# LDOC_sch.net
KiCad netlist of a schematic drawn in Altium Designer
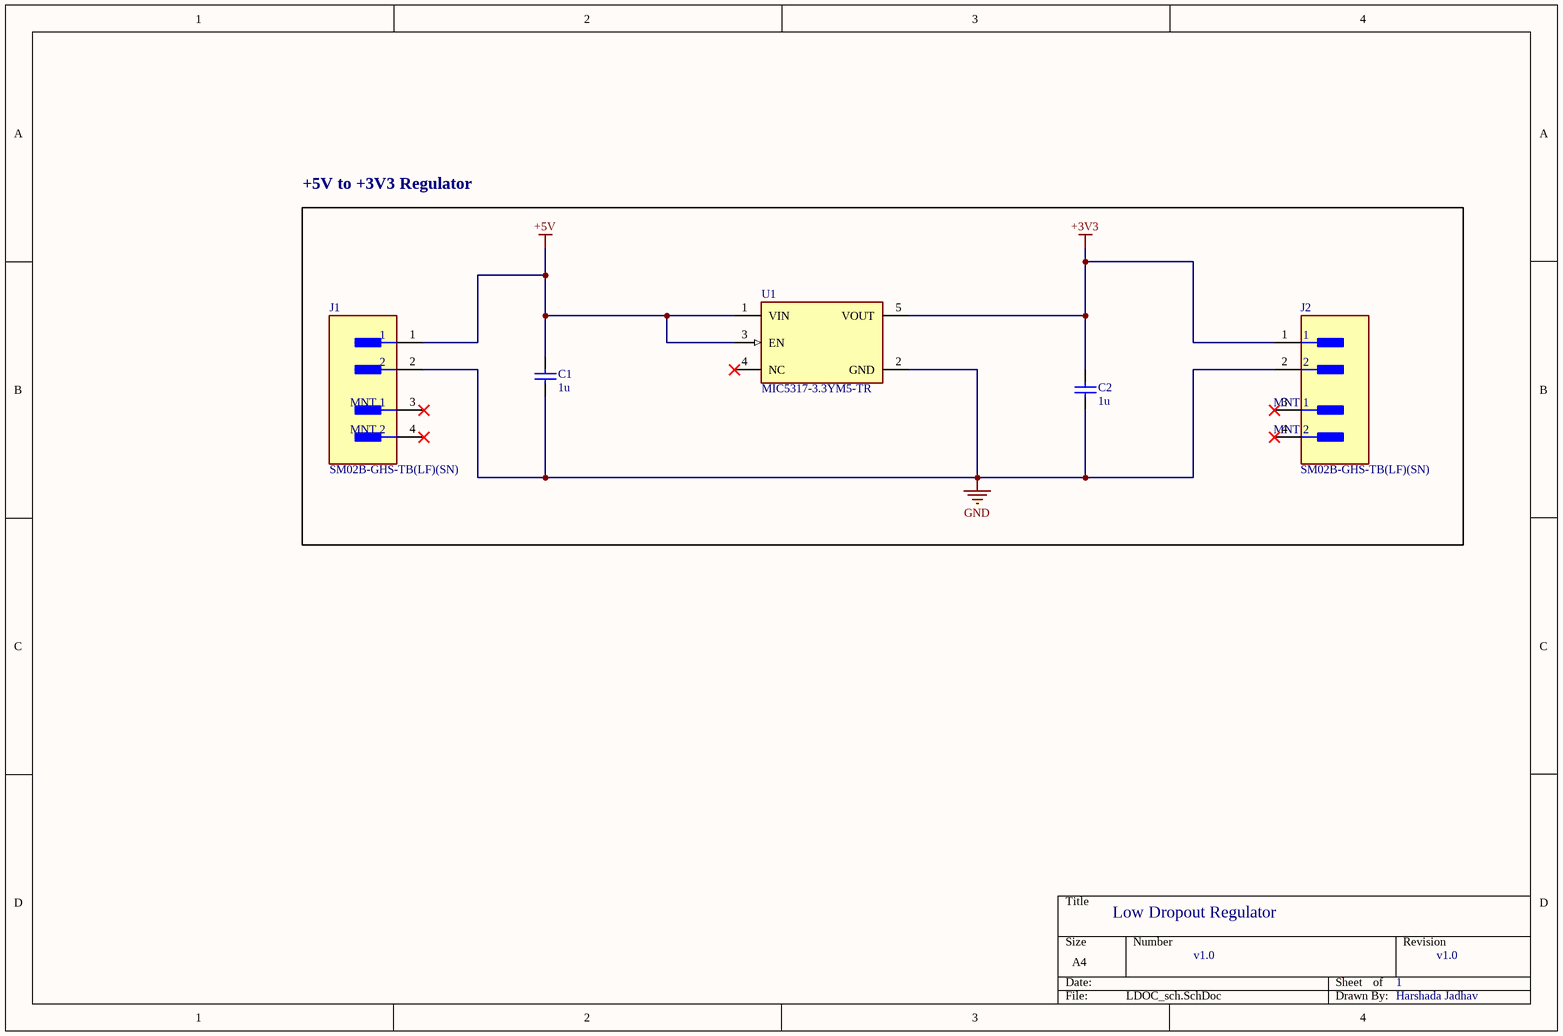
[diagram p0: LDOC_sch.SchDoc]

(export (version "E")
  (design (tool "Eeschema 10.0.6"))
  (components
    (comp (ref "C1")
      (value "1u")
      (footprint "CAPC2013X145X50ML20T25")
      (fields (field (name "PART NUMBER") "C0805C105K8RALTU") (field (name "MANUFACTURER") "Kemet"))
      (libsource (lib "Altium Content Vault") (part "CAP"))
    )
    (comp (ref "C2")
      (value "1u")
      (footprint "CAPC2013X145X50ML20T25")
      (fields (field (name "PART NUMBER") "C0805C105K8RALTU") (field (name "MANUFACTURER") "Kemet"))
      (libsource (lib "Altium Content Vault") (part "CAP"))
    )
    (comp (ref "J1")
      (value "SM02B-GHS-TB(LF)(SN)")
      (footprint "FP-SM02B-GHS-TB_LF_SN-MFG")
      (description "CONN HEADER SMD R/A 2POS 1.25MM")
      (libsource (lib "Altium Content Vault") (part "56ec3178a87b3978bdc1b3682cd516a"))
    )
    (comp (ref "J2")
      (value "SM02B-GHS-TB(LF)(SN)")
      (footprint "FP-SM02B-GHS-TB_LF_SN-MFG")
      (description "CONN HEADER SMD R/A 2POS 1.25MM")
      (libsource (lib "") (part "56ec3178a87b3978bdc1b3682cd516a_1"))
    )
    (comp (ref "U1")
      (value "MIC5317-3.3YM5-TR")
      (footprint "FP-SOT23-5LD-PL-1-MFG")
      (description "IC REG LINEAR 3.3V 150MA SOT23-5")
      (libsource (lib "Altium Content Vault") (part "0a093dae7315cdc977fd108dde87457"))
    )
  )
  (nets
    (net (code "1") (name "+3V3") (class "Default")
      (node (ref "C2") (pin "1") (pinfunction "1_1") (pintype "passive"))
      (node (ref "J2") (pin "1") (pinfunction "1_1") (pintype "passive"))
      (node (ref "U1") (pin "5") (pinfunction "VOUT_5") (pintype "power_in"))
    )
    (net (code "2") (name "+5V") (class "Default")
      (node (ref "C1") (pin "1") (pinfunction "1_1") (pintype "passive"))
      (node (ref "J1") (pin "1") (pinfunction "1_1") (pintype "passive"))
      (node (ref "U1") (pin "1") (pinfunction "VIN_1") (pintype "power_in"))
      (node (ref "U1") (pin "3") (pinfunction "EN_3") (pintype "input"))
    )
    (net (code "3") (name "GND") (class "Default")
      (node (ref "C1") (pin "2") (pinfunction "2_2") (pintype "passive"))
      (node (ref "C2") (pin "2") (pinfunction "2_2") (pintype "passive"))
      (node (ref "J1") (pin "2") (pinfunction "2_2") (pintype "passive"))
      (node (ref "J2") (pin "2") (pinfunction "2_2") (pintype "passive"))
      (node (ref "U1") (pin "2") (pinfunction "GND_2") (pintype "power_in"))
    )
    (net (code "4") (name "unconnected-(J1-MNT_1-Pad3)") (class "Default")
      (node (ref "J1") (pin "3") (pinfunction "MNT_1_3") (pintype "passive+no_connect"))
    )
    (net (code "5") (name "unconnected-(J1-MNT_2-Pad4)") (class "Default")
      (node (ref "J1") (pin "4") (pinfunction "MNT_2_4") (pintype "passive+no_connect"))
    )
    (net (code "6") (name "unconnected-(J2-MNT_1-Pad3)") (class "Default")
      (node (ref "J2") (pin "3") (pinfunction "MNT_1_3") (pintype "passive+no_connect"))
    )
    (net (code "7") (name "unconnected-(J2-MNT_2-Pad4)") (class "Default")
      (node (ref "J2") (pin "4") (pinfunction "MNT_2_4") (pintype "passive+no_connect"))
    )
    (net (code "8") (name "unconnected-(U1-NC-Pad4)") (class "Default")
      (node (ref "U1") (pin "4") (pinfunction "NC_4") (pintype "passive+no_connect"))
    )
  )
)
